# RasPi-BplusHAT_CamSlot.net
KiCad netlist of a schematic drawn in EAGLE
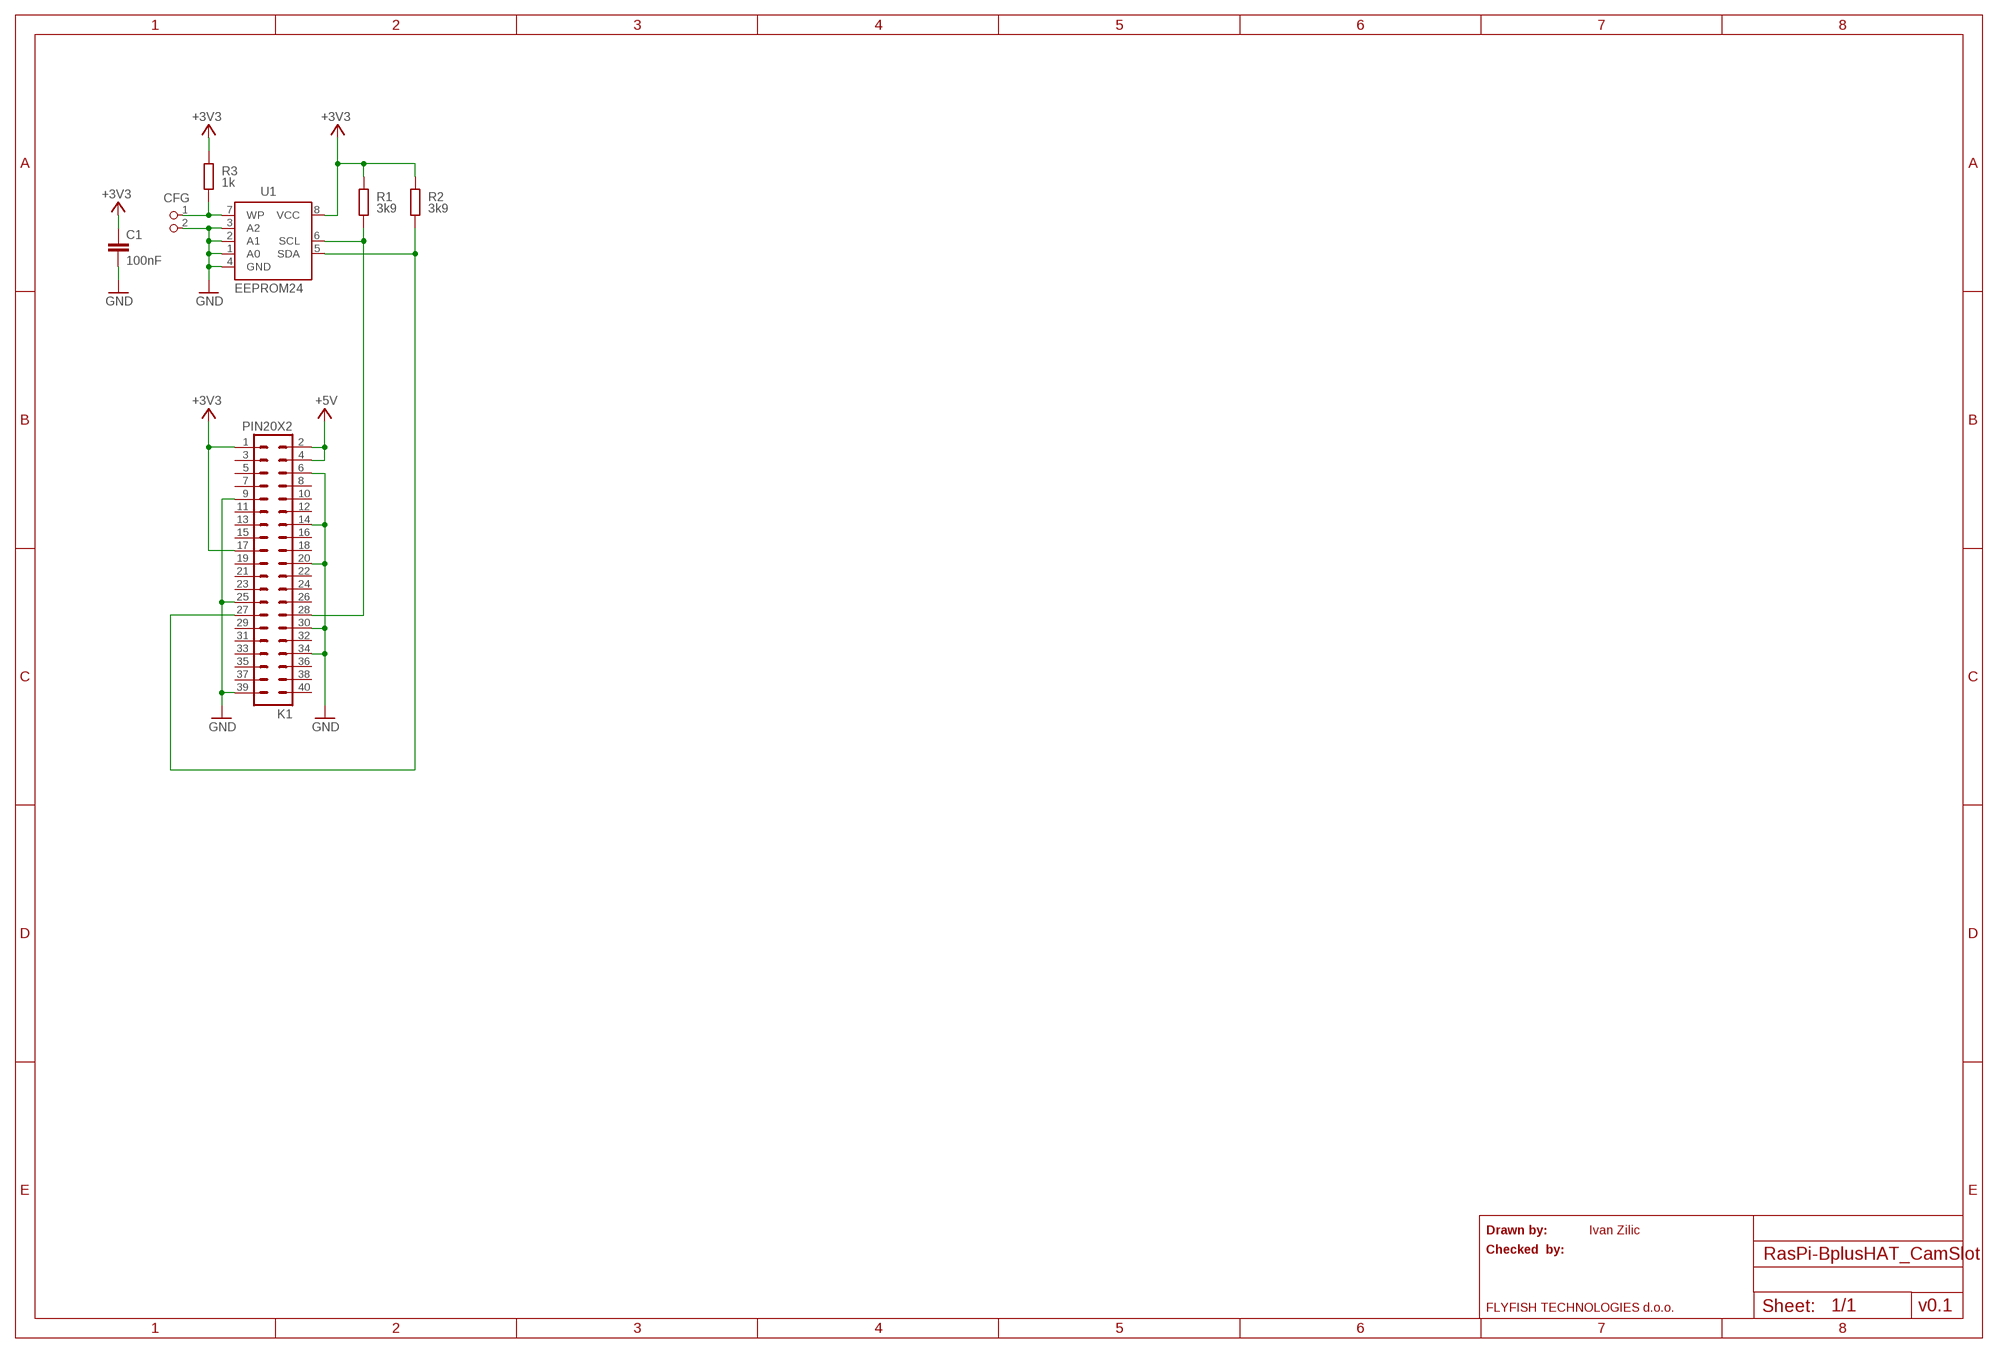
[diagram p0: schematic, sheet 1]

(export (version "E")
  (design (tool "Eeschema 10.0.6"))
  (components
    (comp (ref "C1")
      (value "100nF")
      (footprint "eagle-import:C0805K")
      (libsource (lib "eagle-import") (part "C-EUC0805K"))
    )
    (comp (ref "CFG")
      (value "PIN2_100")
      (footprint "eagle-import:PIN_W_2")
      (libsource (lib "eagle-import") (part "PIN2_100"))
    )
    (comp (ref "K1")
      (value "PIN20X2")
      (footprint "eagle-import:PIN_20X2")
      (libsource (lib "eagle-import") (part "PIN20X2"))
    )
    (comp (ref "R1")
      (value "3k9")
      (footprint "eagle-import:M0805")
      (fields (field (name "TOLERANCE") "5%"))
      (libsource (lib "eagle-import") (part "R-EU_M0805"))
    )
    (comp (ref "R2")
      (value "3k9")
      (footprint "eagle-import:M0805")
      (fields (field (name "TOLERANCE") "5%"))
      (libsource (lib "eagle-import") (part "R-EU_M0805"))
    )
    (comp (ref "R3")
      (value "1k")
      (footprint "eagle-import:M0805")
      (fields (field (name "TOLERANCE") "5%"))
      (libsource (lib "eagle-import") (part "R-EU_M0805"))
    )
    (comp (ref "U1")
      (value "EEPROM24")
      (footprint "eagle-import:SOIC8")
      (libsource (lib "eagle-import") (part "EEPROM24"))
    )
  )
  (nets
    (net (code "1") (name "+3V3") (class "Default")
      (node (ref "C1") (pin "1") (pinfunction "1_1") (pintype "passive"))
      (node (ref "K1") (pin "1") (pinfunction "1_1") (pintype "passive"))
      (node (ref "K1") (pin "17") (pinfunction "17_17") (pintype "passive"))
      (node (ref "R1") (pin "2") (pinfunction "2_2") (pintype "passive"))
      (node (ref "R2") (pin "2") (pinfunction "2_2") (pintype "passive"))
      (node (ref "R3") (pin "2") (pinfunction "2_2") (pintype "passive"))
      (node (ref "U1") (pin "8") (pinfunction "VCC_8") (pintype "power_in"))
    )
    (net (code "2") (name "+5V") (class "Default")
      (node (ref "K1") (pin "2") (pinfunction "2_2") (pintype "passive"))
      (node (ref "K1") (pin "4") (pinfunction "4_4") (pintype "passive"))
    )
    (net (code "3") (name "GND") (class "Default")
      (node (ref "C1") (pin "2") (pinfunction "2_2") (pintype "passive"))
      (node (ref "CFG") (pin "2") (pinfunction "2_2") (pintype "passive"))
      (node (ref "K1") (pin "14") (pinfunction "14_14") (pintype "passive"))
      (node (ref "K1") (pin "20") (pinfunction "20_20") (pintype "passive"))
      (node (ref "K1") (pin "25") (pinfunction "25_25") (pintype "passive"))
      (node (ref "K1") (pin "30") (pinfunction "30_30") (pintype "passive"))
      (node (ref "K1") (pin "34") (pinfunction "34_34") (pintype "passive"))
      (node (ref "K1") (pin "39") (pinfunction "39_39") (pintype "passive"))
      (node (ref "K1") (pin "6") (pinfunction "6_6") (pintype "passive"))
      (node (ref "K1") (pin "9") (pinfunction "9_9") (pintype "passive"))
      (node (ref "U1") (pin "1") (pinfunction "A0_1") (pintype "input"))
      (node (ref "U1") (pin "2") (pinfunction "A1_2") (pintype "input"))
      (node (ref "U1") (pin "3") (pinfunction "A2_3") (pintype "input"))
      (node (ref "U1") (pin "4") (pinfunction "GND_4") (pintype "power_in"))
    )
    (net (code "4") (name "Net-(U1-SCL)") (class "Default")
      (node (ref "K1") (pin "28") (pinfunction "28_28") (pintype "passive"))
      (node (ref "R1") (pin "1") (pinfunction "1_1") (pintype "passive"))
      (node (ref "U1") (pin "6") (pinfunction "SCL_6") (pintype "input"))
    )
    (net (code "5") (name "Net-(U1-SDA)") (class "Default")
      (node (ref "K1") (pin "27") (pinfunction "27_27") (pintype "passive"))
      (node (ref "R2") (pin "1") (pinfunction "1_1") (pintype "passive"))
      (node (ref "U1") (pin "5") (pinfunction "SDA_5") (pintype "bidirectional"))
    )
    (net (code "6") (name "Net-(U1-WP)") (class "Default")
      (node (ref "CFG") (pin "1") (pinfunction "1_1") (pintype "passive"))
      (node (ref "R3") (pin "1") (pinfunction "1_1") (pintype "passive"))
      (node (ref "U1") (pin "7") (pinfunction "WP_7") (pintype "input"))
    )
    (net (code "7") (name "unconnected-(K1-Pad3)") (class "Default")
      (node (ref "K1") (pin "3") (pinfunction "3_3") (pintype "passive"))
    )
    (net (code "8") (name "unconnected-(K1-Pad5)") (class "Default")
      (node (ref "K1") (pin "5") (pinfunction "5_5") (pintype "passive"))
    )
    (net (code "9") (name "unconnected-(K1-Pad7)") (class "Default")
      (node (ref "K1") (pin "7") (pinfunction "7_7") (pintype "passive"))
    )
    (net (code "10") (name "unconnected-(K1-Pad8)") (class "Default")
      (node (ref "K1") (pin "8") (pinfunction "8_8") (pintype "passive"))
    )
    (net (code "11") (name "unconnected-(K1-Pad10)") (class "Default")
      (node (ref "K1") (pin "10") (pinfunction "10_10") (pintype "passive"))
    )
    (net (code "12") (name "unconnected-(K1-Pad11)") (class "Default")
      (node (ref "K1") (pin "11") (pinfunction "11_11") (pintype "passive"))
    )
    (net (code "13") (name "unconnected-(K1-Pad12)") (class "Default")
      (node (ref "K1") (pin "12") (pinfunction "12_12") (pintype "passive"))
    )
    (net (code "14") (name "unconnected-(K1-Pad13)") (class "Default")
      (node (ref "K1") (pin "13") (pinfunction "13_13") (pintype "passive"))
    )
    (net (code "15") (name "unconnected-(K1-Pad15)") (class "Default")
      (node (ref "K1") (pin "15") (pinfunction "15_15") (pintype "passive"))
    )
    (net (code "16") (name "unconnected-(K1-Pad16)") (class "Default")
      (node (ref "K1") (pin "16") (pinfunction "16_16") (pintype "passive"))
    )
    (net (code "17") (name "unconnected-(K1-Pad18)") (class "Default")
      (node (ref "K1") (pin "18") (pinfunction "18_18") (pintype "passive"))
    )
    (net (code "18") (name "unconnected-(K1-Pad19)") (class "Default")
      (node (ref "K1") (pin "19") (pinfunction "19_19") (pintype "passive"))
    )
    (net (code "19") (name "unconnected-(K1-Pad21)") (class "Default")
      (node (ref "K1") (pin "21") (pinfunction "21_21") (pintype "passive"))
    )
    (net (code "20") (name "unconnected-(K1-Pad22)") (class "Default")
      (node (ref "K1") (pin "22") (pinfunction "22_22") (pintype "passive"))
    )
    (net (code "21") (name "unconnected-(K1-Pad23)") (class "Default")
      (node (ref "K1") (pin "23") (pinfunction "23_23") (pintype "passive"))
    )
    (net (code "22") (name "unconnected-(K1-Pad24)") (class "Default")
      (node (ref "K1") (pin "24") (pinfunction "24_24") (pintype "passive"))
    )
    (net (code "23") (name "unconnected-(K1-Pad26)") (class "Default")
      (node (ref "K1") (pin "26") (pinfunction "26_26") (pintype "passive"))
    )
    (net (code "24") (name "unconnected-(K1-Pad29)") (class "Default")
      (node (ref "K1") (pin "29") (pinfunction "29_29") (pintype "passive"))
    )
    (net (code "25") (name "unconnected-(K1-Pad31)") (class "Default")
      (node (ref "K1") (pin "31") (pinfunction "31_31") (pintype "passive"))
    )
    (net (code "26") (name "unconnected-(K1-Pad32)") (class "Default")
      (node (ref "K1") (pin "32") (pinfunction "32_32") (pintype "passive"))
    )
    (net (code "27") (name "unconnected-(K1-Pad33)") (class "Default")
      (node (ref "K1") (pin "33") (pinfunction "33_33") (pintype "passive"))
    )
    (net (code "28") (name "unconnected-(K1-Pad35)") (class "Default")
      (node (ref "K1") (pin "35") (pinfunction "35_35") (pintype "passive"))
    )
    (net (code "29") (name "unconnected-(K1-Pad36)") (class "Default")
      (node (ref "K1") (pin "36") (pinfunction "36_36") (pintype "passive"))
    )
    (net (code "30") (name "unconnected-(K1-Pad37)") (class "Default")
      (node (ref "K1") (pin "37") (pinfunction "37_37") (pintype "passive"))
    )
    (net (code "31") (name "unconnected-(K1-Pad38)") (class "Default")
      (node (ref "K1") (pin "38") (pinfunction "38_38") (pintype "passive"))
    )
    (net (code "32") (name "unconnected-(K1-Pad40)") (class "Default")
      (node (ref "K1") (pin "40") (pinfunction "40_40") (pintype "passive"))
    )
  )
)
